# STM32F030F4.net
KiCad netlist of a schematic drawn in EAGLE
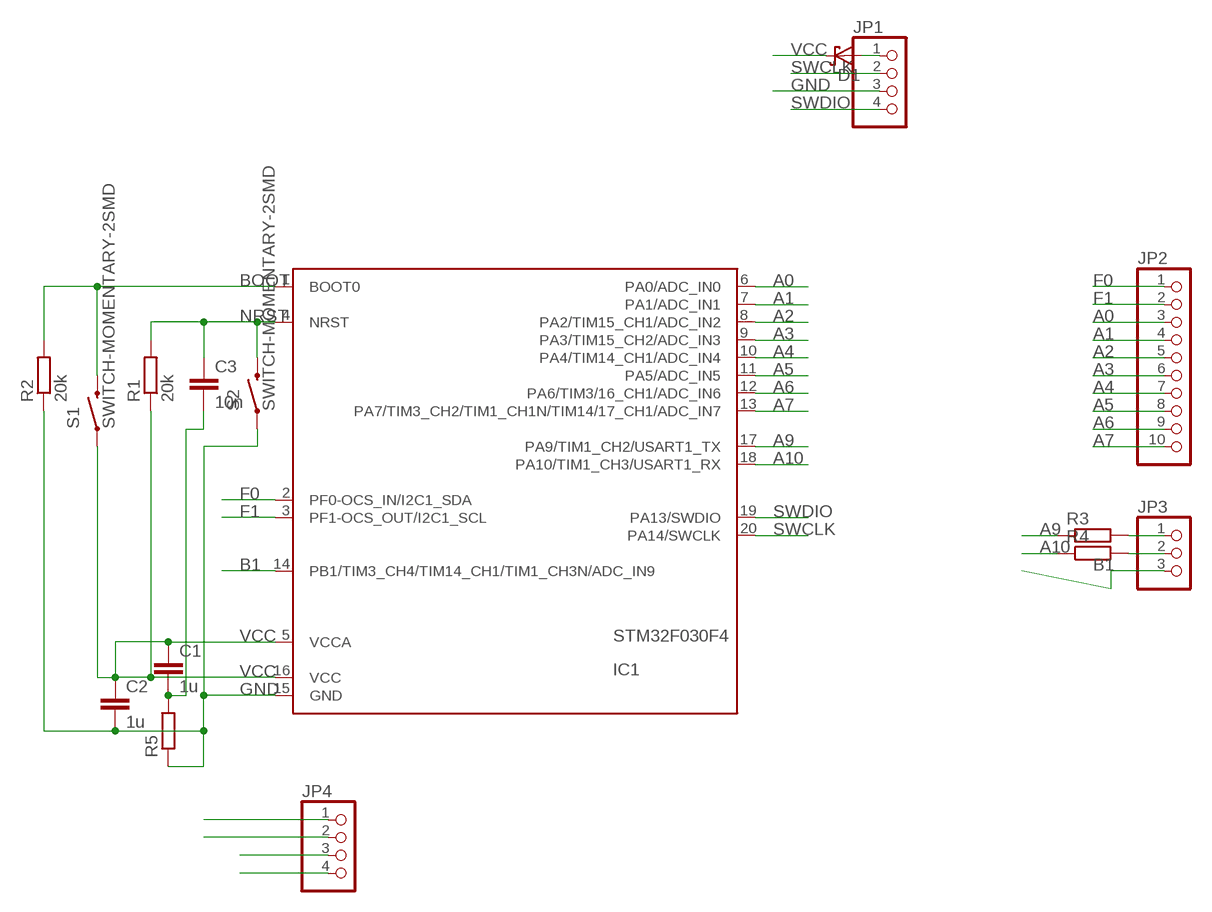
[diagram p0: schematic, sheet 1]

(export (version "E")
  (design (tool "Eeschema 10.0.6"))
  (components
    (comp (ref "C1")
      (value "1u")
      (footprint "eagle-import:C1206")
      (libsource (lib "eagle-import") (part "CAP_1206"))
    )
    (comp (ref "C2")
      (value "1u")
      (footprint "eagle-import:C1206")
      (libsource (lib "eagle-import") (part "CAP_1206"))
    )
    (comp (ref "C3")
      (value "10n")
      (footprint "eagle-import:C1206")
      (libsource (lib "eagle-import") (part "CAP_1206"))
    )
    (comp (ref "D1")
      (value "DIODE-SH_SOD523")
      (footprint "eagle-import:SOD523")
      (libsource (lib "eagle-import") (part "DIODE-SH_SOD523"))
    )
    (comp (ref "IC1")
      (value "STM32F030F4")
      (footprint "eagle-import:TSSOP20")
      (libsource (lib "eagle-import") (part "STM32F030F4"))
    )
    (comp (ref "JP1")
      (value "PINHD-1X4")
      (footprint "eagle-import:1X04")
      (libsource (lib "eagle-import") (part "PINHD-1X4"))
    )
    (comp (ref "JP2")
      (value "PINHD-1X10")
      (footprint "eagle-import:1X10")
      (libsource (lib "eagle-import") (part "PINHD-1X10"))
    )
    (comp (ref "JP3")
      (value "PINHD-1X3")
      (footprint "eagle-import:1X03")
      (libsource (lib "eagle-import") (part "PINHD-1X3"))
    )
    (comp (ref "JP4")
      (value "PINHD-1X4")
      (footprint "eagle-import:1X04")
      (libsource (lib "eagle-import") (part "PINHD-1X4"))
    )
    (comp (ref "R1")
      (value "20k")
      (footprint "eagle-import:R1206")
      (libsource (lib "eagle-import") (part "R_1206"))
    )
    (comp (ref "R2")
      (value "20k")
      (footprint "eagle-import:R1206")
      (libsource (lib "eagle-import") (part "R_1206"))
    )
    (comp (ref "R3")
      (value "R_1206")
      (footprint "eagle-import:R1206")
      (libsource (lib "eagle-import") (part "R_1206"))
    )
    (comp (ref "R4")
      (value "R_1206")
      (footprint "eagle-import:R1206")
      (libsource (lib "eagle-import") (part "R_1206"))
    )
    (comp (ref "R5")
      (value "R_1206")
      (footprint "eagle-import:R1206")
      (libsource (lib "eagle-import") (part "R_1206"))
    )
    (comp (ref "S1")
      (value "SWITCH-MOMENTARY-2SMD")
      (footprint "eagle-import:TACTILE-SWITCH-SMD")
      (libsource (lib "eagle-import") (part "SWITCH-MOMENTARY-2SMD"))
    )
    (comp (ref "S2")
      (value "SWITCH-MOMENTARY-2SMD")
      (footprint "eagle-import:TACTILE-SWITCH-SMD")
      (libsource (lib "eagle-import") (part "SWITCH-MOMENTARY-2SMD"))
    )
  )
  (nets
    (net (code "1") (name "/A0") (class "Default")
      (node (ref "IC1") (pin "6") (pinfunction "PA0/ADC_IN0_6") (pintype "bidirectional"))
      (node (ref "JP2") (pin "3") (pinfunction "3_3") (pintype "passive"))
    )
    (net (code "2") (name "/A1") (class "Default")
      (node (ref "IC1") (pin "7") (pinfunction "PA1/ADC_IN1_7") (pintype "bidirectional"))
      (node (ref "JP2") (pin "4") (pinfunction "4_4") (pintype "passive"))
    )
    (net (code "3") (name "/A2") (class "Default")
      (node (ref "IC1") (pin "8") (pinfunction "PA2/TIM15_CH1/ADC_IN2_8") (pintype "bidirectional"))
      (node (ref "JP2") (pin "5") (pinfunction "5_5") (pintype "passive"))
    )
    (net (code "4") (name "/A3") (class "Default")
      (node (ref "IC1") (pin "9") (pinfunction "PA3/TIM15_CH2/ADC_IN3_9") (pintype "bidirectional"))
      (node (ref "JP2") (pin "6") (pinfunction "6_6") (pintype "passive"))
    )
    (net (code "5") (name "/A4") (class "Default")
      (node (ref "IC1") (pin "10") (pinfunction "PA4/TIM14_CH1/ADC_IN4_10") (pintype "bidirectional"))
      (node (ref "JP2") (pin "7") (pinfunction "7_7") (pintype "passive"))
    )
    (net (code "6") (name "/A5") (class "Default")
      (node (ref "IC1") (pin "11") (pinfunction "PA5/ADC_IN5_11") (pintype "bidirectional"))
      (node (ref "JP2") (pin "8") (pinfunction "8_8") (pintype "passive"))
    )
    (net (code "7") (name "/A6") (class "Default")
      (node (ref "IC1") (pin "12") (pinfunction "PA6/TIM3/16_CH1/ADC_IN6_12") (pintype "bidirectional"))
      (node (ref "JP2") (pin "9") (pinfunction "9_9") (pintype "passive"))
    )
    (net (code "8") (name "/A7") (class "Default")
      (node (ref "IC1") (pin "13") (pinfunction "PA7/TIM3_CH2/TIM1_CH1N/TIM14/17_CH1/ADC_IN7_13") (pintype "bidirectional"))
      (node (ref "JP2") (pin "10") (pinfunction "10_10") (pintype "passive"))
    )
    (net (code "9") (name "/A9") (class "Default")
      (node (ref "IC1") (pin "17") (pinfunction "PA9/TIM1_CH2/USART1_TX_17") (pintype "bidirectional"))
      (node (ref "R3") (pin "1") (pinfunction "1_1") (pintype "passive"))
    )
    (net (code "10") (name "/A10") (class "Default")
      (node (ref "IC1") (pin "18") (pinfunction "PA10/TIM1_CH3/USART1_RX_18") (pintype "bidirectional"))
      (node (ref "R4") (pin "1") (pinfunction "1_1") (pintype "passive"))
    )
    (net (code "11") (name "/B1") (class "Default")
      (node (ref "IC1") (pin "14") (pinfunction "PB1/TIM3_CH4/TIM14_CH1/TIM1_CH3N/ADC_IN9_14") (pintype "bidirectional"))
      (node (ref "JP3") (pin "3") (pinfunction "3_3") (pintype "passive"))
    )
    (net (code "12") (name "/BOOT") (class "Default")
      (node (ref "IC1") (pin "1") (pinfunction "BOOT0_1") (pintype "bidirectional"))
      (node (ref "R2") (pin "2") (pinfunction "2_2") (pintype "passive"))
      (node (ref "S1") (pin "3") (pinfunction "2_3") (pintype "passive"))
    )
    (net (code "13") (name "/F0") (class "Default")
      (node (ref "IC1") (pin "2") (pinfunction "PF0-OCS_IN/I2C1_SDA_2") (pintype "bidirectional"))
      (node (ref "JP2") (pin "1") (pinfunction "1_1") (pintype "passive"))
    )
    (net (code "14") (name "/F1") (class "Default")
      (node (ref "IC1") (pin "3") (pinfunction "PF1-OCS_OUT/I2C1_SCL_3") (pintype "bidirectional"))
      (node (ref "JP2") (pin "2") (pinfunction "2_2") (pintype "passive"))
    )
    (net (code "15") (name "/GND") (class "Default")
      (node (ref "C2") (pin "2") (pinfunction "2_2") (pintype "passive"))
      (node (ref "IC1") (pin "15") (pinfunction "GND_15") (pintype "power_in"))
      (node (ref "JP1") (pin "3") (pinfunction "3_3") (pintype "passive"))
      (node (ref "JP4") (pin "3") (pinfunction "3_3") (pintype "passive"))
      (node (ref "JP4") (pin "4") (pinfunction "4_4") (pintype "passive"))
      (node (ref "R2") (pin "1") (pinfunction "1_1") (pintype "passive"))
      (node (ref "R5") (pin "1") (pinfunction "1_1") (pintype "passive"))
      (node (ref "S2") (pin "1") (pinfunction "1_1") (pintype "passive"))
    )
    (net (code "16") (name "/NRST") (class "Default")
      (node (ref "C3") (pin "1") (pinfunction "1_1") (pintype "passive"))
      (node (ref "IC1") (pin "4") (pinfunction "NRST_4") (pintype "bidirectional"))
      (node (ref "R1") (pin "2") (pinfunction "2_2") (pintype "passive"))
      (node (ref "S2") (pin "3") (pinfunction "2_3") (pintype "passive"))
    )
    (net (code "17") (name "/SWCLK") (class "Default")
      (node (ref "IC1") (pin "20") (pinfunction "PA14/SWCLK_20") (pintype "bidirectional"))
      (node (ref "JP1") (pin "2") (pinfunction "2_2") (pintype "passive"))
    )
    (net (code "18") (name "/SWDIO") (class "Default")
      (node (ref "IC1") (pin "19") (pinfunction "PA13/SWDIO_19") (pintype "bidirectional"))
      (node (ref "JP1") (pin "4") (pinfunction "4_4") (pintype "passive"))
    )
    (net (code "19") (name "/VCC") (class "Default")
      (node (ref "C1") (pin "1") (pinfunction "1_1") (pintype "passive"))
      (node (ref "C2") (pin "1") (pinfunction "1_1") (pintype "passive"))
      (node (ref "D1") (pin "C") (pinfunction "C_C") (pintype "passive"))
      (node (ref "IC1") (pin "16") (pinfunction "VCC_16") (pintype "power_in"))
      (node (ref "IC1") (pin "5") (pinfunction "VCCA_5") (pintype "power_in"))
      (node (ref "JP4") (pin "1") (pinfunction "1_1") (pintype "passive"))
      (node (ref "JP4") (pin "2") (pinfunction "2_2") (pintype "passive"))
      (node (ref "R1") (pin "1") (pinfunction "1_1") (pintype "passive"))
      (node (ref "S1") (pin "1") (pinfunction "1_1") (pintype "passive"))
    )
    (net (code "20") (name "Net-(C1-Pad2)") (class "Default")
      (node (ref "C1") (pin "2") (pinfunction "2_2") (pintype "passive"))
      (node (ref "C3") (pin "2") (pinfunction "2_2") (pintype "passive"))
      (node (ref "R5") (pin "2") (pinfunction "2_2") (pintype "passive"))
    )
    (net (code "21") (name "Net-(D1-PadA)") (class "Default")
      (node (ref "D1") (pin "A") (pinfunction "A_A") (pintype "passive"))
      (node (ref "JP1") (pin "1") (pinfunction "1_1") (pintype "passive"))
    )
    (net (code "22") (name "Net-(JP3-Pad1)") (class "Default")
      (node (ref "JP3") (pin "1") (pinfunction "1_1") (pintype "passive"))
      (node (ref "R3") (pin "2") (pinfunction "2_2") (pintype "passive"))
    )
    (net (code "23") (name "Net-(JP3-Pad2)") (class "Default")
      (node (ref "JP3") (pin "2") (pinfunction "2_2") (pintype "passive"))
      (node (ref "R4") (pin "2") (pinfunction "2_2") (pintype "passive"))
    )
  )
)
